# EEPROM.net
KiCad netlist of a schematic drawn in Altium Designer
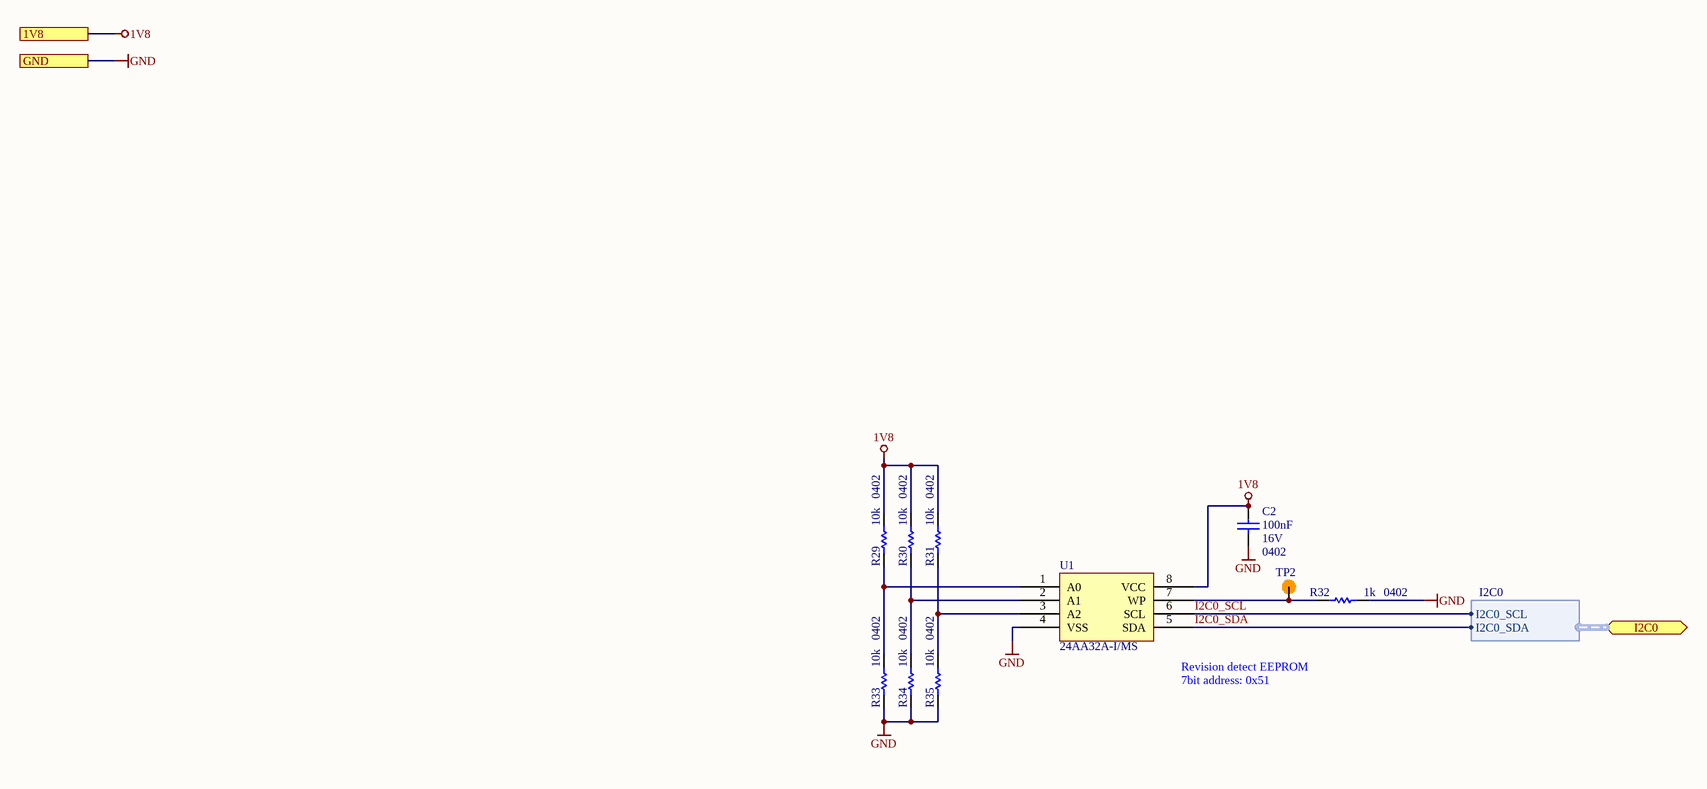
[diagram p0: EEPROM.SchDoc]

(export (version "E")
  (design (tool "Eeschema 10.0.6"))
  (components
    (comp (ref "C2")
      (value "100nF")
      (footprint "CAPC0402(1005)60_L")
      (description "CAP CER 0.1UF 16V X7R 0402 10%")
      (fields
        (field (name "VOLTAGE RATING") "16V")
        (field (name "CASE/PACKAGE") "0402")
        (field (name "TOLERANCE") "10%")
        (field (name "Comment") "CL05B104KO5NFNC")
      )
      (libsource (lib "Luxonis LLC") (part "GRM188R61C475KAAJD"))
    )
    (comp (ref "R29")
      (value "10k")
      (footprint "RESC0402(1005)_L")
      (description "RES SMD 10K OHM 1% 1/16W 0402")
      (fields
        (field (name "CASE/PACKAGE") "0402")
        (field (name "TOLERANCE") "1%")
        (field (name "Comment") "RC0402FR-1310KL")
      )
      (libsource (lib "Luxonis LLC") (part "RC0402FR-0722RL_1"))
    )
    (comp (ref "R30")
      (value "10k")
      (footprint "RESC0402(1005)_L")
      (description "RES SMD 10K OHM 1% 1/16W 0402")
      (fields
        (field (name "CASE/PACKAGE") "0402")
        (field (name "TOLERANCE") "1%")
        (field (name "Comment") "RC0402FR-1310KL")
      )
      (libsource (lib "Luxonis LLC") (part "RC0402FR-0722RL_1"))
    )
    (comp (ref "R31")
      (value "10k")
      (footprint "RESC0402(1005)_L")
      (description "RES SMD 10K OHM 1% 1/16W 0402")
      (fields
        (field (name "CASE/PACKAGE") "0402")
        (field (name "TOLERANCE") "1%")
        (field (name "Comment") "RC0402FR-1310KL")
      )
      (libsource (lib "Luxonis LLC") (part "RC0402FR-0722RL_1"))
    )
    (comp (ref "R32")
      (value "1k")
      (footprint "RESC0402(1005)_L")
      (description "RES SMD 1K OHM 1% 1/16W 0402")
      (fields
        (field (name "CASE/PACKAGE") "0402")
        (field (name "TOLERANCE") "1%")
        (field (name "Comment") "RC0402FR-071KL")
      )
      (libsource (lib "Luxonis LLC") (part "Default resistor symbol"))
    )
    (comp (ref "R33")
      (value "10k")
      (footprint "RESC0402(1005)_L")
      (description "RES SMD 10K OHM 1% 1/16W 0402")
      (fields
        (field (name "CASE/PACKAGE") "0402")
        (field (name "TOLERANCE") "1%")
        (field (name "Comment") "RC0402FR-1310KL")
      )
      (libsource (lib "Luxonis LLC") (part "RC0402FR-0722RL_1"))
    )
    (comp (ref "R34")
      (value "10k")
      (footprint "RESC0402(1005)_L")
      (description "RES SMD 10K OHM 1% 1/16W 0402")
      (fields
        (field (name "CASE/PACKAGE") "0402")
        (field (name "TOLERANCE") "1%")
        (field (name "Comment") "RC0402FR-1310KL")
      )
      (libsource (lib "Luxonis LLC") (part "RC0402FR-0722RL_1"))
    )
    (comp (ref "R35")
      (value "10k")
      (footprint "RESC0402(1005)_L")
      (description "RES SMD 10K OHM 1% 1/16W 0402")
      (fields
        (field (name "CASE/PACKAGE") "0402")
        (field (name "TOLERANCE") "1%")
        (field (name "Comment") "RC0402FR-1310KL")
      )
      (libsource (lib "Luxonis LLC") (part "RC0402FR-0722RL_1"))
    )
    (comp (ref "TP2")
      (value "TEST_POINT")
      (footprint "TP075_150_NS")
      (libsource (lib "Luxonis LLC") (part "TEST_POINT"))
    )
    (comp (ref "U1")
      (value "24AA32A-I/MS")
      (footprint "24AA32A-I/MS")
      (description "IC EEPROM 32K I2C 400KHZ 8MSOP Memory IC 32Kb (4K x 8) I²C 400kHz 900ns 8-MSOP")
      (libsource (lib "Luxonis LLC") (part "24AA32A-I/MS"))
    )
  )
  (nets
    (net (code "2") (name "/I2C0_SCL") (class "Default")
      (node (ref "U1") (pin "6") (pinfunction "SCL_6") (pintype "passive"))
    )
    (net (code "3") (name "/I2C0_SDA") (class "Default")
      (node (ref "U1") (pin "5") (pinfunction "SDA_5") (pintype "passive"))
    )
    (net (code "5") (name "1V8") (class "Default")
      (node (ref "C2") (pin "2") (pinfunction "2_2") (pintype "passive"))
      (node (ref "R29") (pin "2") (pinfunction "2_2") (pintype "passive"))
      (node (ref "R30") (pin "2") (pinfunction "2_2") (pintype "passive"))
      (node (ref "R31") (pin "2") (pinfunction "2_2") (pintype "passive"))
      (node (ref "U1") (pin "8") (pinfunction "VCC_8") (pintype "passive"))
    )
    (net (code "6") (name "GND") (class "Default")
      (node (ref "C2") (pin "1") (pinfunction "1_1") (pintype "passive"))
      (node (ref "R32") (pin "1") (pinfunction "1_1") (pintype "passive"))
      (node (ref "R33") (pin "1") (pinfunction "1_1") (pintype "passive"))
      (node (ref "R34") (pin "1") (pinfunction "1_1") (pintype "passive"))
      (node (ref "R35") (pin "1") (pinfunction "1_1") (pintype "passive"))
      (node (ref "U1") (pin "4") (pinfunction "VSS_4") (pintype "passive"))
    )
    (net (code "7") (name "Net-(U1-A0)") (class "Default")
      (node (ref "R29") (pin "1") (pinfunction "1_1") (pintype "passive"))
      (node (ref "R33") (pin "2") (pinfunction "2_2") (pintype "passive"))
      (node (ref "U1") (pin "1") (pinfunction "A0_1") (pintype "passive"))
    )
    (net (code "8") (name "Net-(U1-A1)") (class "Default")
      (node (ref "R30") (pin "1") (pinfunction "1_1") (pintype "passive"))
      (node (ref "R34") (pin "2") (pinfunction "2_2") (pintype "passive"))
      (node (ref "U1") (pin "2") (pinfunction "A1_2") (pintype "passive"))
    )
    (net (code "9") (name "Net-(U1-A2)") (class "Default")
      (node (ref "R31") (pin "1") (pinfunction "1_1") (pintype "passive"))
      (node (ref "R35") (pin "2") (pinfunction "2_2") (pintype "passive"))
      (node (ref "U1") (pin "3") (pinfunction "A2_3") (pintype "passive"))
    )
    (net (code "10") (name "Net-(U1-WP)") (class "Default")
      (node (ref "R32") (pin "2") (pinfunction "2_2") (pintype "passive"))
      (node (ref "TP2") (pin "1") (pintype "passive"))
      (node (ref "U1") (pin "7") (pinfunction "WP_7") (pintype "passive"))
    )
  )
)
